# SparkFun_Pressure_Sensor_BMP581_Qwiic_Mi.net
KiCad netlist of a schematic drawn in EAGLE
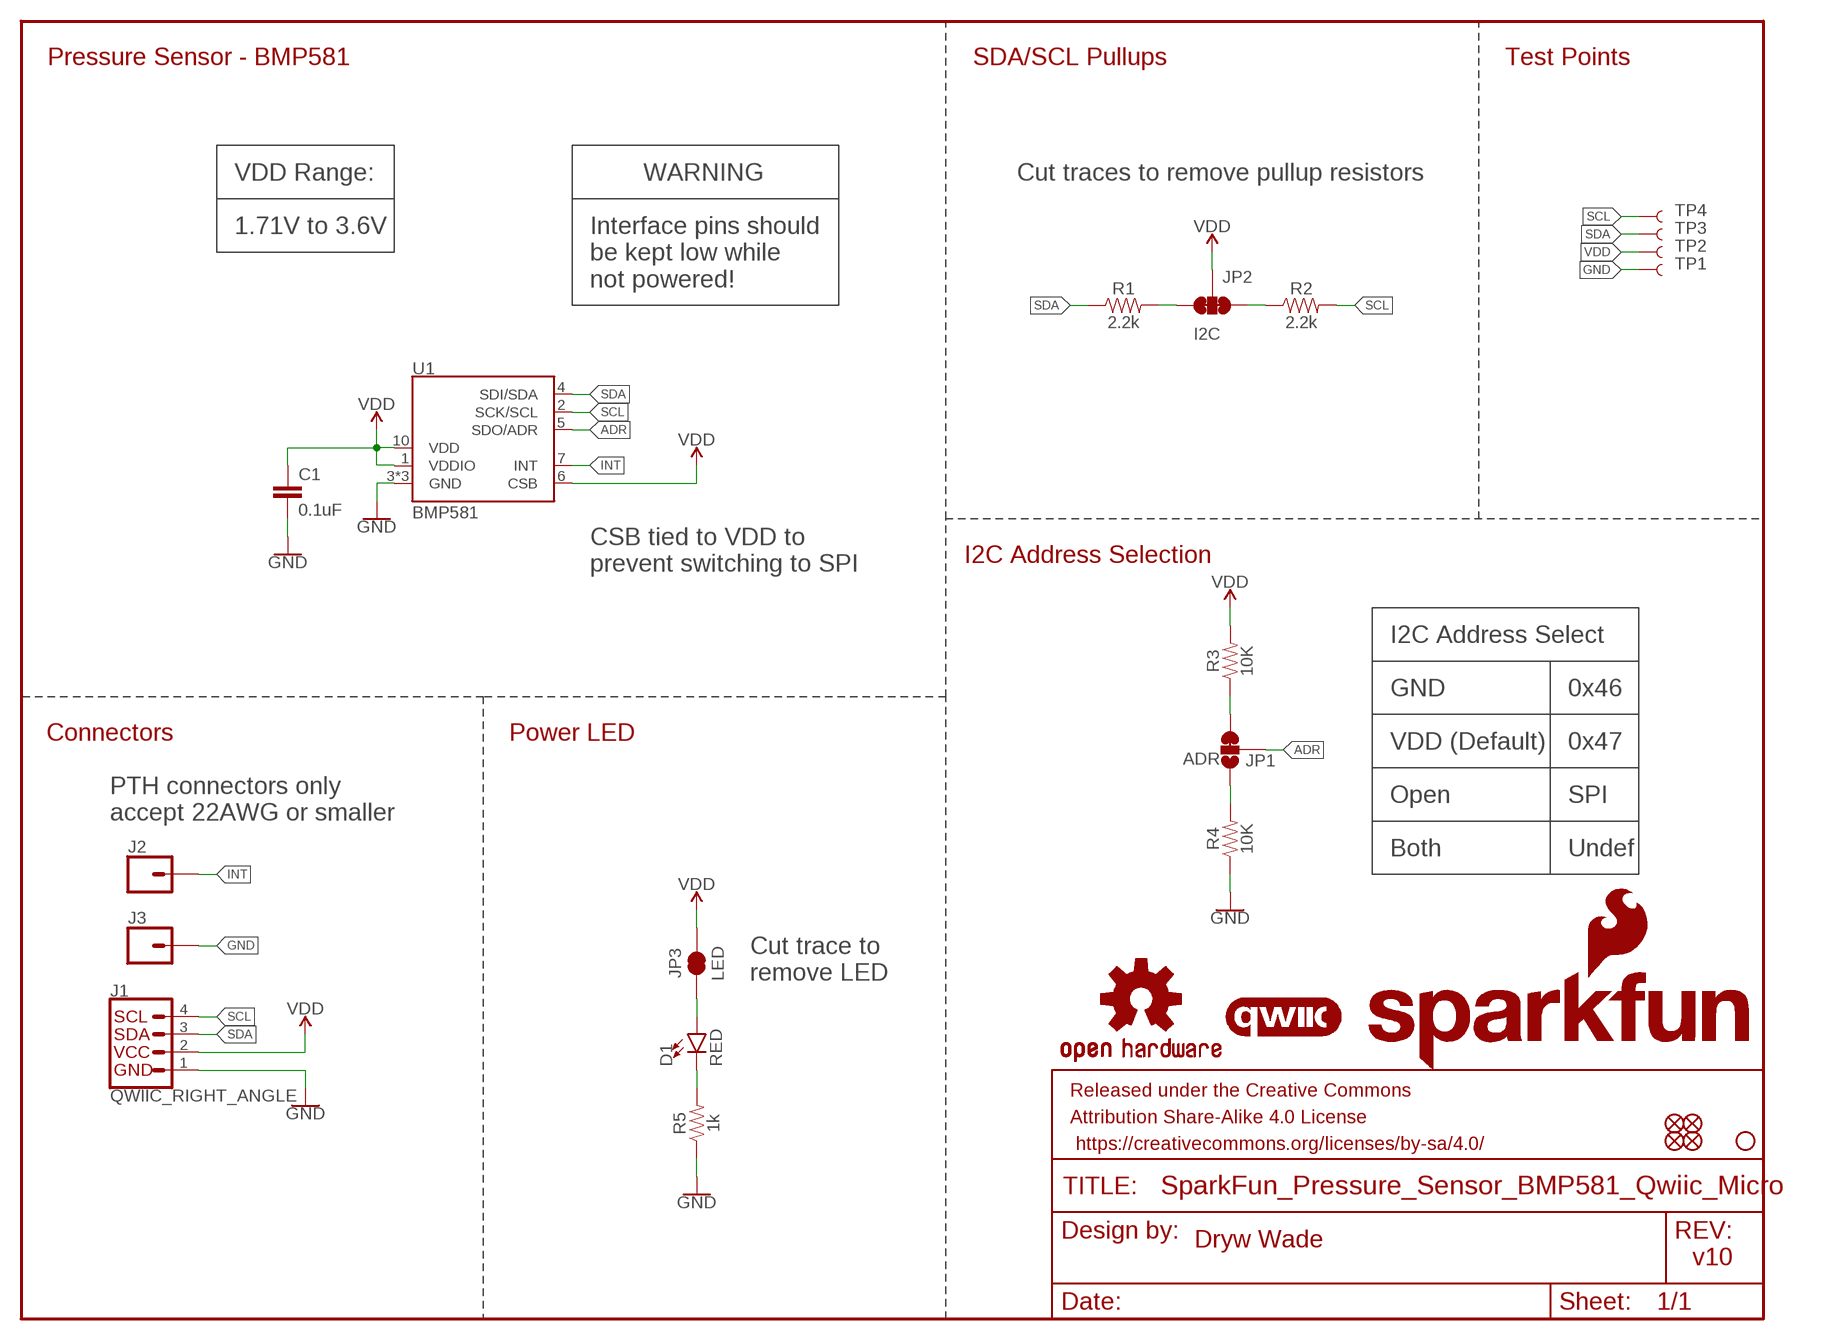
[diagram p0: schematic, sheet 1]

(export (version "E")
  (design (tool "Eeschema 10.0.6"))
  (components
    (comp (ref "C1")
      (value "0.1uF")
      (footprint "eagle-import:0402-TIGHT")
      (libsource (lib "eagle-import") (part "0.1UF-0402T-6.3V-10%-X7R"))
    )
    (comp (ref "D1")
      (value "RED")
      (footprint "eagle-import:LED-0402")
      (libsource (lib "eagle-import") (part "LED-RED_0402"))
    )
    (comp (ref "FD1")
      (value "FIDUCIALUFIDUCIAL")
      (footprint "eagle-import:FIDUCIAL-MICRO")
      (libsource (lib "eagle-import") (part "FIDUCIALUFIDUCIAL"))
    )
    (comp (ref "FD2")
      (value "FIDUCIALUFIDUCIAL")
      (footprint "eagle-import:FIDUCIAL-MICRO")
      (libsource (lib "eagle-import") (part "FIDUCIALUFIDUCIAL"))
    )
    (comp (ref "FD3")
      (value "FIDUCIALUFIDUCIAL")
      (footprint "eagle-import:FIDUCIAL-MICRO")
      (libsource (lib "eagle-import") (part "FIDUCIALUFIDUCIAL"))
    )
    (comp (ref "FD4")
      (value "FIDUCIALUFIDUCIAL")
      (footprint "eagle-import:FIDUCIAL-MICRO")
      (libsource (lib "eagle-import") (part "FIDUCIALUFIDUCIAL"))
    )
    (comp (ref "FRAME1")
      (value "FRAME-LETTER")
      (footprint "eagle-import:CREATIVE_COMMONS")
      (libsource (lib "eagle-import") (part "FRAME-LETTER"))
    )
    (comp (ref "H1")
      (value "STAND-OFF")
      (footprint "eagle-import:STAND-OFF")
      (libsource (lib "eagle-import") (part "STAND-OFF"))
    )
    (comp (ref "J1")
      (value "QWIIC_RIGHT_ANGLE")
      (footprint "eagle-import:JST04_1MM_RA")
      (libsource (lib "eagle-import") (part "QWIIC_CONNECTORJS-1MM"))
    )
    (comp (ref "J2")
      (value "CONN_01_1MM")
      (footprint "eagle-import:1X01_1MM_NO_SILK")
      (libsource (lib "eagle-import") (part "CONN_01_1MM"))
    )
    (comp (ref "J3")
      (value "CONN_01_1MM")
      (footprint "eagle-import:1X01_1MM_NO_SILK")
      (libsource (lib "eagle-import") (part "CONN_01_1MM"))
    )
    (comp (ref "JP1")
      (value "ADR")
      (footprint "eagle-import:SMT-JUMPER_3_1-NC_TRACE_SILK")
      (libsource (lib "eagle-import") (part "JUMPER-SMT_3_1-NC_TRACE_SILK"))
    )
    (comp (ref "JP2")
      (value "I2C")
      (footprint "eagle-import:SMT-JUMPER_3_2-NC_TRACE_SILK")
      (libsource (lib "eagle-import") (part "JUMPER-SMT_3_2-NC_TRACE_SILK"))
    )
    (comp (ref "JP3")
      (value "LED")
      (footprint "eagle-import:SMT-JUMPER_2_NC_TRACE_SILK")
      (libsource (lib "eagle-import") (part "JUMPER-SMT_2_NC_TRACE_SILK"))
    )
    (comp (ref "LOGO1")
      (value "OSHW-LOGOMINI")
      (footprint "eagle-import:OSHW-LOGO-MINI")
      (libsource (lib "eagle-import") (part "OSHW-LOGOMINI"))
    )
    (comp (ref "LOGO2")
      (value "SFE_LOGO_FLAME.1_INCH")
      (footprint "eagle-import:SFE_LOGO_FLAME_.1")
      (libsource (lib "eagle-import") (part "SFE_LOGO_FLAME.1_INCH"))
    )
    (comp (ref "LOGO3")
      (value "QWIIC_LOGO_3MM")
      (footprint "eagle-import:QWIIC_3MM")
      (libsource (lib "eagle-import") (part "QWIIC_LOGO_3MM"))
    )
    (comp (ref "LOGO4")
      (value "SFE_LOGO_NAMEBLANK")
      (footprint "eagle-import:BLANK")
      (libsource (lib "eagle-import") (part "SFE_LOGO_NAMEBLANK"))
    )
    (comp (ref "R1")
      (value "2.2k")
      (footprint "eagle-import:0402-TIGHT")
      (libsource (lib "eagle-import") (part "2.2KOHM-0402T-1/16W-1%"))
    )
    (comp (ref "R2")
      (value "2.2k")
      (footprint "eagle-import:0402-TIGHT")
      (libsource (lib "eagle-import") (part "2.2KOHM-0402T-1/16W-1%"))
    )
    (comp (ref "R3")
      (value "10K")
      (footprint "eagle-import:0402-TIGHT")
      (libsource (lib "eagle-import") (part "10KOHM-0402-1/10W-0.1%"))
    )
    (comp (ref "R4")
      (value "10K")
      (footprint "eagle-import:0402-TIGHT")
      (libsource (lib "eagle-import") (part "10KOHM-0402-1/10W-0.1%"))
    )
    (comp (ref "R5")
      (value "1k")
      (footprint "eagle-import:0402-TIGHT")
      (libsource (lib "eagle-import") (part "1KOHM-0402T-1/16W-1%"))
    )
    (comp (ref "TP1")
      (value "TEST-POINT3")
      (footprint "eagle-import:PAD.03X.03")
      (libsource (lib "eagle-import") (part "TEST-POINT3"))
    )
    (comp (ref "TP2")
      (value "TEST-POINT3")
      (footprint "eagle-import:PAD.03X.03")
      (libsource (lib "eagle-import") (part "TEST-POINT3"))
    )
    (comp (ref "TP3")
      (value "TEST-POINT3")
      (footprint "eagle-import:PAD.03X.03")
      (libsource (lib "eagle-import") (part "TEST-POINT3"))
    )
    (comp (ref "TP4")
      (value "TEST-POINT3")
      (footprint "eagle-import:PAD.03X.03")
      (libsource (lib "eagle-import") (part "TEST-POINT3"))
    )
    (comp (ref "U1")
      (value "BMP581")
      (footprint "eagle-import:BMP581")
      (libsource (lib "eagle-import") (part "BMP581"))
    )
  )
  (nets
    (net (code "1") (name "ADR") (class "Default")
      (node (ref "JP1") (pin "2") (pinfunction "2_2") (pintype "passive"))
      (node (ref "U1") (pin "5") (pinfunction "SDO/ADR_5") (pintype "bidirectional"))
    )
    (net (code "2") (name "GND") (class "Default")
      (node (ref "C1") (pin "2") (pinfunction "2_2") (pintype "passive"))
      (node (ref "J1") (pin "1") (pinfunction "1_1") (pintype "power_in"))
      (node (ref "J3") (pin "1") (pinfunction "1_1") (pintype "passive"))
      (node (ref "R4") (pin "1") (pinfunction "1_1") (pintype "passive"))
      (node (ref "R5") (pin "1") (pinfunction "1_1") (pintype "passive"))
      (node (ref "TP1") (pin "1") (pinfunction "1_1") (pintype "bidirectional"))
      (node (ref "U1") (pin "3") (pinfunction "GND_3") (pintype "power_in"))
      (node (ref "U1") (pin "8") (pinfunction "GND_8") (pintype "power_in"))
      (node (ref "U1") (pin "9") (pinfunction "GND_9") (pintype "power_in"))
    )
    (net (code "3") (name "INT") (class "Default")
      (node (ref "J2") (pin "1") (pinfunction "1_1") (pintype "passive"))
      (node (ref "U1") (pin "7") (pinfunction "INT_7") (pintype "output"))
    )
    (net (code "4") (name "Net-(D1-PadA)") (class "Default")
      (node (ref "D1") (pin "A") (pinfunction "A_A") (pintype "passive"))
      (node (ref "JP3") (pin "1") (pinfunction "1_1") (pintype "passive"))
    )
    (net (code "5") (name "Net-(D1-PadC)") (class "Default")
      (node (ref "D1") (pin "C") (pinfunction "C_C") (pintype "passive"))
      (node (ref "R5") (pin "2") (pinfunction "2_2") (pintype "passive"))
    )
    (net (code "6") (name "Net-(JP1-Pad1)") (class "Default")
      (node (ref "JP1") (pin "1") (pinfunction "1_1") (pintype "passive"))
      (node (ref "R4") (pin "2") (pinfunction "2_2") (pintype "passive"))
    )
    (net (code "7") (name "Net-(JP1-Pad3)") (class "Default")
      (node (ref "JP1") (pin "3") (pinfunction "3_3") (pintype "passive"))
      (node (ref "R3") (pin "1") (pinfunction "1_1") (pintype "passive"))
    )
    (net (code "8") (name "Net-(JP2-Pad1)") (class "Default")
      (node (ref "JP2") (pin "1") (pinfunction "1_1") (pintype "passive"))
      (node (ref "R2") (pin "1") (pinfunction "1_1") (pintype "passive"))
    )
    (net (code "9") (name "Net-(JP2-Pad3)") (class "Default")
      (node (ref "JP2") (pin "3") (pinfunction "3_3") (pintype "passive"))
      (node (ref "R1") (pin "2") (pinfunction "2_2") (pintype "passive"))
    )
    (net (code "10") (name "SCL") (class "Default")
      (node (ref "J1") (pin "4") (pinfunction "4_4") (pintype "passive"))
      (node (ref "R2") (pin "2") (pinfunction "2_2") (pintype "passive"))
      (node (ref "TP4") (pin "1") (pinfunction "1_1") (pintype "bidirectional"))
      (node (ref "U1") (pin "2") (pinfunction "SCK/SCL_2") (pintype "bidirectional"))
    )
    (net (code "11") (name "SDA") (class "Default")
      (node (ref "J1") (pin "3") (pinfunction "3_3") (pintype "passive"))
      (node (ref "R1") (pin "1") (pinfunction "1_1") (pintype "passive"))
      (node (ref "TP3") (pin "1") (pinfunction "1_1") (pintype "bidirectional"))
      (node (ref "U1") (pin "4") (pinfunction "SDI/SDA_4") (pintype "bidirectional"))
    )
    (net (code "12") (name "VDD") (class "Default")
      (node (ref "C1") (pin "1") (pinfunction "1_1") (pintype "passive"))
      (node (ref "J1") (pin "2") (pinfunction "2_2") (pintype "power_in"))
      (node (ref "JP2") (pin "2") (pinfunction "2_2") (pintype "passive"))
      (node (ref "JP3") (pin "2") (pinfunction "2_2") (pintype "passive"))
      (node (ref "R3") (pin "2") (pinfunction "2_2") (pintype "passive"))
      (node (ref "TP2") (pin "1") (pinfunction "1_1") (pintype "bidirectional"))
      (node (ref "U1") (pin "1") (pinfunction "VDDIO_1") (pintype "power_in"))
      (node (ref "U1") (pin "10") (pinfunction "VDD_10") (pintype "power_in"))
      (node (ref "U1") (pin "6") (pinfunction "CSB_6") (pintype "input"))
    )
  )
)
